# detector_ne602_v2.net
KiCad netlist of a schematic drawn in EAGLE
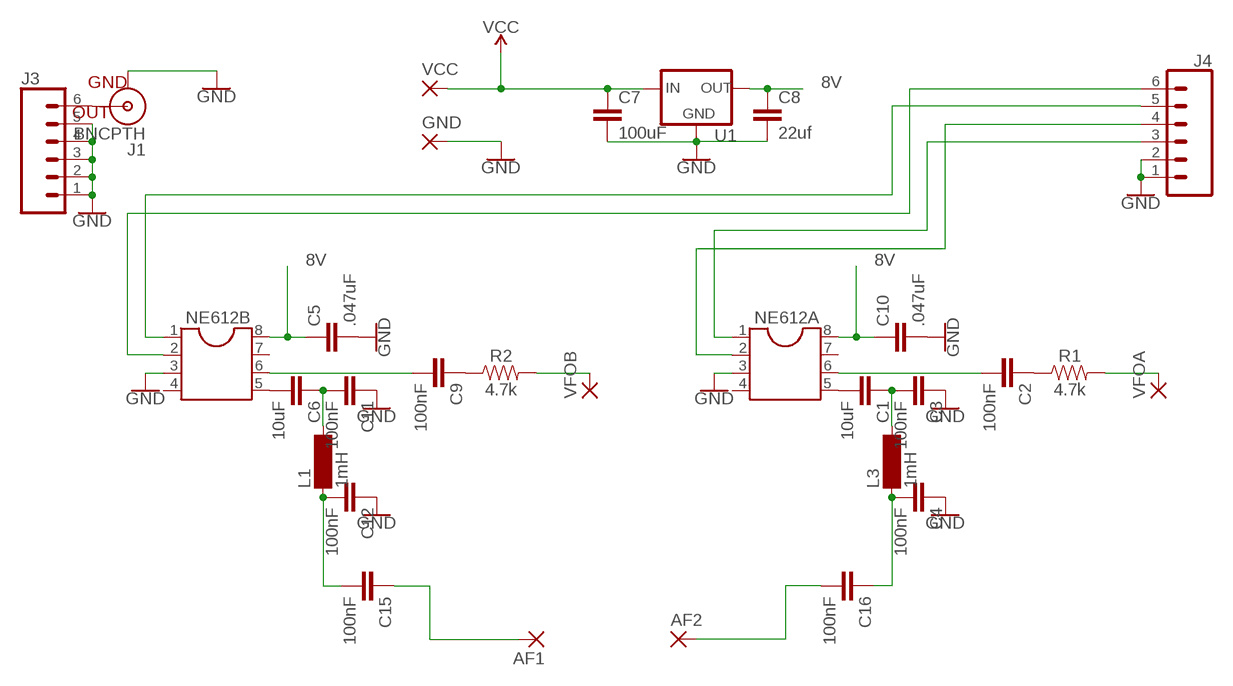
[diagram p0: schematic, sheet 1]

(export (version "E")
  (design (tool "Eeschema 10.0.6"))
  (components
    (comp (ref "AF1")
      (value "3,17/1,1")
      (footprint "eagle-import:3,17_1,1")
      (libsource (lib "eagle-import") (part "3,17/1,1"))
    )
    (comp (ref "AF2")
      (value "3,17/1,1")
      (footprint "eagle-import:3,17_1,1")
      (libsource (lib "eagle-import") (part "3,17/1,1"))
    )
    (comp (ref "C1")
      (value "10uF")
      (footprint "eagle-import:C5B3.5")
      (libsource (lib "eagle-import") (part "C5/3.5"))
    )
    (comp (ref "C2")
      (value "100nF")
      (footprint "eagle-import:C5B3.5")
      (libsource (lib "eagle-import") (part "C5/3.5"))
    )
    (comp (ref "C3")
      (value "100nF")
      (footprint "eagle-import:C5B3.5")
      (libsource (lib "eagle-import") (part "C5/3.5"))
    )
    (comp (ref "C4")
      (value "100nF")
      (footprint "eagle-import:C5B3.5")
      (libsource (lib "eagle-import") (part "C5/3.5"))
    )
    (comp (ref "C5")
      (value ".047uF")
      (footprint "eagle-import:C5B3.5")
      (libsource (lib "eagle-import") (part "C5/3.5"))
    )
    (comp (ref "C6")
      (value "10uF")
      (footprint "eagle-import:C5B3.5")
      (libsource (lib "eagle-import") (part "C5/3.5"))
    )
    (comp (ref "C7")
      (value "100uF")
      (footprint "eagle-import:C5B3.5")
      (libsource (lib "eagle-import") (part "C5/3.5"))
    )
    (comp (ref "C8")
      (value "22uf")
      (footprint "eagle-import:C5B3.5")
      (libsource (lib "eagle-import") (part "C5/3.5"))
    )
    (comp (ref "C9")
      (value "100nF")
      (footprint "eagle-import:C5B3.5")
      (libsource (lib "eagle-import") (part "C5/3.5"))
    )
    (comp (ref "C10")
      (value ".047uF")
      (footprint "eagle-import:C5B3.5")
      (libsource (lib "eagle-import") (part "C5/3.5"))
    )
    (comp (ref "C11")
      (value "100nF")
      (footprint "eagle-import:C5B3.5")
      (libsource (lib "eagle-import") (part "C5/3.5"))
    )
    (comp (ref "C12")
      (value "100nF")
      (footprint "eagle-import:C5B3.5")
      (libsource (lib "eagle-import") (part "C5/3.5"))
    )
    (comp (ref "C15")
      (value "100nF")
      (footprint "eagle-import:C5B3.5")
      (libsource (lib "eagle-import") (part "C5/3.5"))
    )
    (comp (ref "C16")
      (value "100nF")
      (footprint "eagle-import:C5B3.5")
      (libsource (lib "eagle-import") (part "C5/3.5"))
    )
    (comp (ref "GND")
      (value "3,17/1,1")
      (footprint "eagle-import:3,17_1,1")
      (libsource (lib "eagle-import") (part "3,17/1,1"))
    )
    (comp (ref "J1")
      (value "BNCPTH")
      (footprint "eagle-import:BNC")
      (libsource (lib "eagle-import") (part "BNCPTH"))
    )
    (comp (ref "J3")
      (value "CONN_06SILK_FEMALE_PTH")
      (footprint "eagle-import:1X06")
      (libsource (lib "eagle-import") (part "CONN_06SILK_FEMALE_PTH"))
    )
    (comp (ref "J4")
      (value "CONN_06SILK_FEMALE_PTH")
      (footprint "eagle-import:1X06")
      (libsource (lib "eagle-import") (part "CONN_06SILK_FEMALE_PTH"))
    )
    (comp (ref "L1")
      (value "1mH")
      (footprint "eagle-import:BS75")
      (libsource (lib "eagle-import") (part "BS75"))
    )
    (comp (ref "L3")
      (value "1mH")
      (footprint "eagle-import:BS75")
      (libsource (lib "eagle-import") (part "BS75"))
    )
    (comp (ref "NE612A")
      (value "DIL8")
      (footprint "eagle-import:DIL08")
      (libsource (lib "eagle-import") (part "DIL8"))
    )
    (comp (ref "NE612B")
      (value "DIL8")
      (footprint "eagle-import:DIL08")
      (libsource (lib "eagle-import") (part "DIL8"))
    )
    (comp (ref "R1")
      (value "4.7k")
      (footprint "eagle-import:AXIAL-0.3")
      (libsource (lib "eagle-import") (part "1KOHM-HORIZ-1/4W-1%"))
    )
    (comp (ref "R2")
      (value "4.7k")
      (footprint "eagle-import:AXIAL-0.3")
      (libsource (lib "eagle-import") (part "1KOHM-HORIZ-1/4W-1%"))
    )
    (comp (ref "U1")
      (value "V_REG_78XXTO-92_UNTESTED")
      (footprint "eagle-import:TO-92")
      (libsource (lib "eagle-import") (part "V_REG_78XXTO-92_UNTESTED"))
    )
    (comp (ref "VCC")
      (value "3,17/1,1")
      (footprint "eagle-import:3,17_1,1")
      (libsource (lib "eagle-import") (part "3,17/1,1"))
    )
    (comp (ref "VFOA")
      (value "3,17/1,1")
      (footprint "eagle-import:3,17_1,1")
      (libsource (lib "eagle-import") (part "3,17/1,1"))
    )
    (comp (ref "VFOB")
      (value "3,17/1,1")
      (footprint "eagle-import:3,17_1,1")
      (libsource (lib "eagle-import") (part "3,17/1,1"))
    )
  )
  (nets
    (net (code "1") (name "/8V") (class "Default")
      (node (ref "C10") (pin "1") (pinfunction "1_1") (pintype "passive"))
      (node (ref "C5") (pin "1") (pinfunction "1_1") (pintype "passive"))
      (node (ref "C8") (pin "1") (pinfunction "1_1") (pintype "passive"))
      (node (ref "NE612A") (pin "8") (pinfunction "8_8") (pintype "passive"))
      (node (ref "NE612B") (pin "8") (pinfunction "8_8") (pintype "passive"))
      (node (ref "U1") (pin "1") (pinfunction "OUT_1") (pintype "passive"))
    )
    (net (code "2") (name "GND") (class "Default")
      (node (ref "C10") (pin "2") (pinfunction "2_2") (pintype "passive"))
      (node (ref "C11") (pin "1") (pinfunction "1_1") (pintype "passive"))
      (node (ref "C12") (pin "1") (pinfunction "1_1") (pintype "passive"))
      (node (ref "C3") (pin "1") (pinfunction "1_1") (pintype "passive"))
      (node (ref "C4") (pin "1") (pinfunction "1_1") (pintype "passive"))
      (node (ref "C5") (pin "2") (pinfunction "2_2") (pintype "passive"))
      (node (ref "C7") (pin "2") (pinfunction "2_2") (pintype "passive"))
      (node (ref "C8") (pin "2") (pinfunction "2_2") (pintype "passive"))
      (node (ref "GND") (pin "1") (pinfunction "P_1") (pintype "passive"))
      (node (ref "J1") (pin "GND") (pinfunction "GND_GND") (pintype "bidirectional"))
      (node (ref "J3") (pin "1") (pinfunction "1_1") (pintype "passive"))
      (node (ref "J3") (pin "2") (pinfunction "2_2") (pintype "passive"))
      (node (ref "J3") (pin "3") (pinfunction "3_3") (pintype "passive"))
      (node (ref "J3") (pin "4") (pinfunction "4_4") (pintype "passive"))
      (node (ref "J3") (pin "5") (pinfunction "5_5") (pintype "passive"))
      (node (ref "J4") (pin "1") (pinfunction "1_1") (pintype "passive"))
      (node (ref "J4") (pin "2") (pinfunction "2_2") (pintype "passive"))
      (node (ref "NE612A") (pin "3") (pinfunction "3_3") (pintype "passive"))
      (node (ref "NE612B") (pin "3") (pinfunction "3_3") (pintype "passive"))
      (node (ref "U1") (pin "2") (pinfunction "GND_2") (pintype "input"))
    )
    (net (code "3") (name "Net-(AF1-P)") (class "Default")
      (node (ref "AF1") (pin "1") (pinfunction "P_1") (pintype "passive"))
      (node (ref "C15") (pin "1") (pinfunction "1_1") (pintype "passive"))
    )
    (net (code "4") (name "Net-(AF2-P)") (class "Default")
      (node (ref "AF2") (pin "1") (pinfunction "P_1") (pintype "passive"))
      (node (ref "C16") (pin "2") (pinfunction "2_2") (pintype "passive"))
    )
    (net (code "5") (name "Net-(C1-Pad1)") (class "Default")
      (node (ref "C1") (pin "1") (pinfunction "1_1") (pintype "passive"))
      (node (ref "C3") (pin "2") (pinfunction "2_2") (pintype "passive"))
      (node (ref "L3") (pin "2") (pinfunction "2_2") (pintype "passive"))
    )
    (net (code "6") (name "Net-(C1-Pad2)") (class "Default")
      (node (ref "C1") (pin "2") (pinfunction "2_2") (pintype "passive"))
      (node (ref "NE612A") (pin "5") (pinfunction "5_5") (pintype "passive"))
    )
    (net (code "7") (name "Net-(C2-Pad2)") (class "Default")
      (node (ref "C2") (pin "2") (pinfunction "2_2") (pintype "passive"))
      (node (ref "NE612A") (pin "6") (pinfunction "6_6") (pintype "passive"))
    )
    (net (code "8") (name "Net-(C6-Pad2)") (class "Default")
      (node (ref "C6") (pin "2") (pinfunction "2_2") (pintype "passive"))
      (node (ref "NE612B") (pin "5") (pinfunction "5_5") (pintype "passive"))
    )
    (net (code "9") (name "Net-(C9-Pad2)") (class "Default")
      (node (ref "C9") (pin "2") (pinfunction "2_2") (pintype "passive"))
      (node (ref "NE612B") (pin "6") (pinfunction "6_6") (pintype "passive"))
    )
    (net (code "10") (name "Net-(C11-Pad2)") (class "Default")
      (node (ref "C11") (pin "2") (pinfunction "2_2") (pintype "passive"))
      (node (ref "C6") (pin "1") (pinfunction "1_1") (pintype "passive"))
      (node (ref "L1") (pin "2") (pinfunction "2_2") (pintype "passive"))
    )
    (net (code "11") (name "Net-(C12-Pad2)") (class "Default")
      (node (ref "C12") (pin "2") (pinfunction "2_2") (pintype "passive"))
      (node (ref "C15") (pin "2") (pinfunction "2_2") (pintype "passive"))
      (node (ref "L1") (pin "1") (pinfunction "1_1") (pintype "passive"))
    )
    (net (code "12") (name "Net-(C16-Pad1)") (class "Default")
      (node (ref "C16") (pin "1") (pinfunction "1_1") (pintype "passive"))
      (node (ref "C4") (pin "2") (pinfunction "2_2") (pintype "passive"))
      (node (ref "L3") (pin "1") (pinfunction "1_1") (pintype "passive"))
    )
    (net (code "13") (name "Net-(J1-OUT)") (class "Default")
      (node (ref "J1") (pin "S") (pinfunction "OUT_S") (pintype "bidirectional"))
      (node (ref "J3") (pin "6") (pinfunction "6_6") (pintype "passive"))
    )
    (net (code "14") (name "Net-(J4-Pad3)") (class "Default")
      (node (ref "J4") (pin "3") (pinfunction "3_3") (pintype "passive"))
      (node (ref "NE612A") (pin "1") (pinfunction "1_1") (pintype "passive"))
    )
    (net (code "15") (name "Net-(J4-Pad4)") (class "Default")
      (node (ref "J4") (pin "4") (pinfunction "4_4") (pintype "passive"))
      (node (ref "NE612A") (pin "2") (pinfunction "2_2") (pintype "passive"))
    )
    (net (code "16") (name "Net-(J4-Pad5)") (class "Default")
      (node (ref "J4") (pin "5") (pinfunction "5_5") (pintype "passive"))
      (node (ref "NE612B") (pin "1") (pinfunction "1_1") (pintype "passive"))
    )
    (net (code "17") (name "Net-(J4-Pad6)") (class "Default")
      (node (ref "J4") (pin "6") (pinfunction "6_6") (pintype "passive"))
      (node (ref "NE612B") (pin "2") (pinfunction "2_2") (pintype "passive"))
    )
    (net (code "18") (name "Net-(R1-1)") (class "Default")
      (node (ref "C2") (pin "1") (pinfunction "1_1") (pintype "passive"))
      (node (ref "R1") (pin "P$1") (pinfunction "1_P$1") (pintype "passive"))
    )
    (net (code "19") (name "Net-(R1-2)") (class "Default")
      (node (ref "R1") (pin "P$2") (pinfunction "2_P$2") (pintype "passive"))
      (node (ref "VFOA") (pin "1") (pinfunction "P_1") (pintype "passive"))
    )
    (net (code "20") (name "Net-(R2-1)") (class "Default")
      (node (ref "C9") (pin "1") (pinfunction "1_1") (pintype "passive"))
      (node (ref "R2") (pin "P$1") (pinfunction "1_P$1") (pintype "passive"))
    )
    (net (code "21") (name "Net-(R2-2)") (class "Default")
      (node (ref "R2") (pin "P$2") (pinfunction "2_P$2") (pintype "passive"))
      (node (ref "VFOB") (pin "1") (pinfunction "P_1") (pintype "passive"))
    )
    (net (code "22") (name "VCC") (class "Default")
      (node (ref "C7") (pin "1") (pinfunction "1_1") (pintype "passive"))
      (node (ref "U1") (pin "3") (pinfunction "IN_3") (pintype "input"))
      (node (ref "VCC") (pin "1") (pinfunction "P_1") (pintype "passive"))
    )
    (net (code "23") (name "unconnected-(NE612A-Pad4)") (class "Default")
      (node (ref "NE612A") (pin "4") (pinfunction "4_4") (pintype "passive"))
    )
    (net (code "24") (name "unconnected-(NE612A-Pad7)") (class "Default")
      (node (ref "NE612A") (pin "7") (pinfunction "7_7") (pintype "passive"))
    )
    (net (code "25") (name "unconnected-(NE612B-Pad4)") (class "Default")
      (node (ref "NE612B") (pin "4") (pinfunction "4_4") (pintype "passive"))
    )
    (net (code "26") (name "unconnected-(NE612B-Pad7)") (class "Default")
      (node (ref "NE612B") (pin "7") (pinfunction "7_7") (pintype "passive"))
    )
  )
)
